# ATmega328-ED.net
KiCad netlist of a schematic drawn in Altium Designer
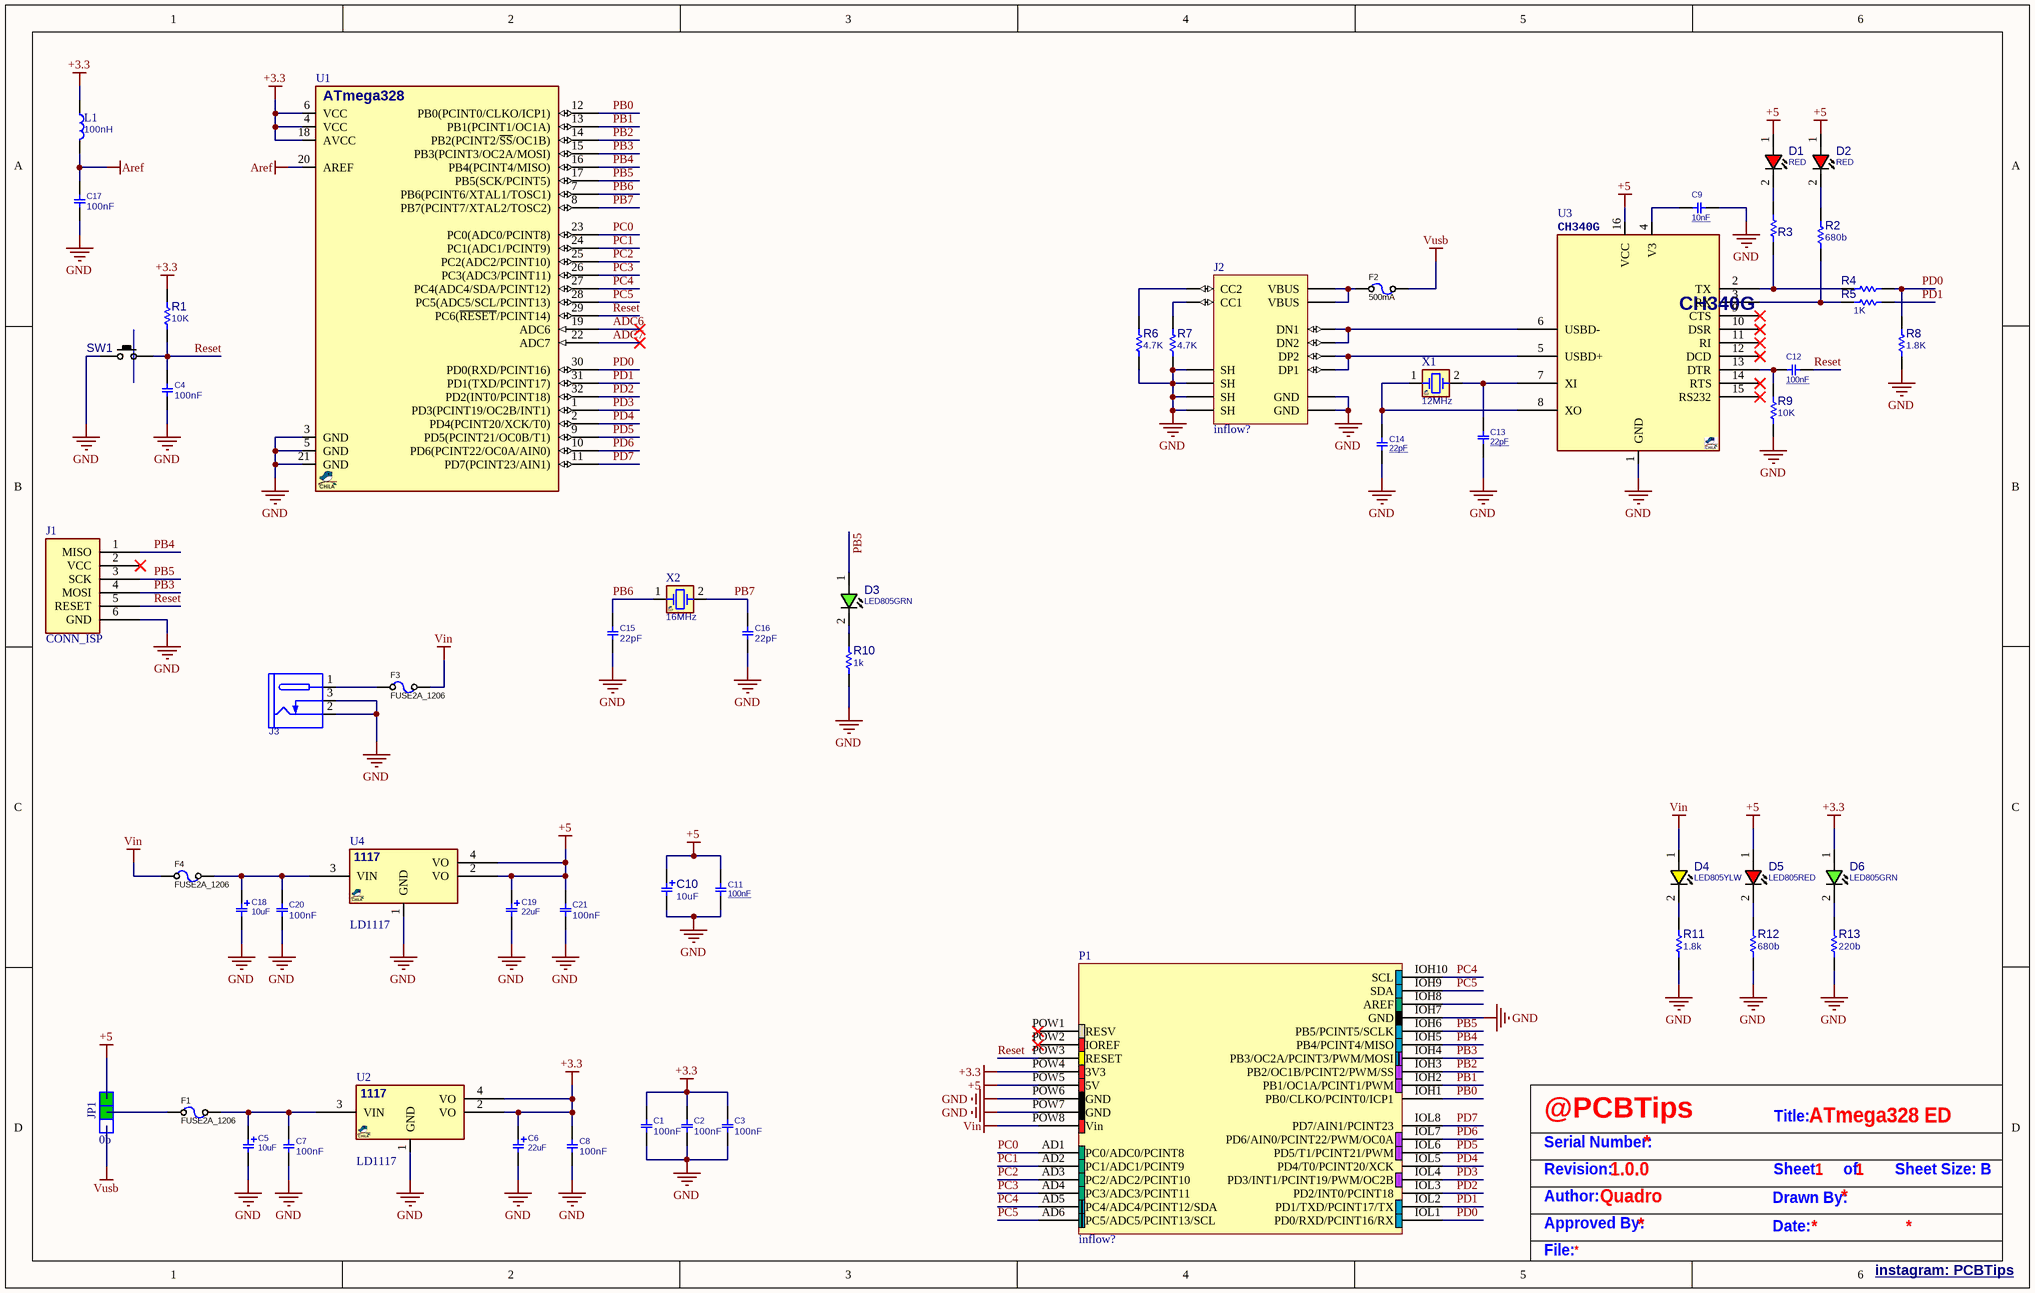
[diagram p0: ATmega328-ED.SchDoc]

(export (version "E")
  (design (tool "Eeschema 10.0.6"))
  (components
    (comp (ref "C1")
      (value "100nF")
      (footprint "C0805")
      (description "CAP, MLCC")
      (fields (field (name "MANF_P#") "MANF_PART#"))
      (libsource (lib "AVR_RCS") (part "CAP_SMD_MLCC_0805"))
    )
    (comp (ref "C2")
      (value "100nF")
      (footprint "C0805")
      (description "CAP, MLCC")
      (fields (field (name "MANF_P#") "MANF_PART#"))
      (libsource (lib "AVR_RCS") (part "CAP_SMD_MLCC_0805"))
    )
    (comp (ref "C3")
      (value "100nF")
      (footprint "C0805")
      (description "CAP, MLCC")
      (fields (field (name "MANF_P#") "MANF_PART#"))
      (libsource (lib "AVR_RCS") (part "CAP_SMD_MLCC_0805"))
    )
    (comp (ref "C4")
      (value "100nF")
      (footprint "C0805")
      (description "CAP, MLCC")
      (fields (field (name "MANF_P#") "MANF_PART#"))
      (libsource (lib "AVR_RCS") (part "CAP_SMD_MLCC_0805"))
    )
    (comp (ref "C5")
      (value "10uF")
      (footprint "C_TN_2012")
      (description "CAP, SMD, TAN")
      (fields (field (name "MANF") "VISHAY") (field (name "MANF_P#") "T55A106M6R3C0300"))
      (libsource (lib "AVR_RCS") (part "CAP_SMD_TAN_4"))
    )
    (comp (ref "C6")
      (value "22uF")
      (footprint "C_TN_2012")
      (description "CAP, SMD, TAN")
      (fields (field (name "MANF") "VISHAY") (field (name "MANF_P#") "T55A106M6R3C0300"))
      (libsource (lib "AVR_RCS") (part "CAP_SMD_TAN_4"))
    )
    (comp (ref "C7")
      (value "100nF")
      (footprint "C1206")
      (description "CAP, MLCC")
      (fields (field (name "MANF_P#") "MANF_PART#"))
      (libsource (lib "AVR_RCS") (part "CAP_SMD_MLCC_1206"))
    )
    (comp (ref "C8")
      (value "100nF")
      (footprint "C1206")
      (description "CAP, MLCC")
      (fields (field (name "MANF_P#") "MANF_PART#"))
      (libsource (lib "AVR_RCS") (part "CAP_SMD_MLCC_1206"))
    )
    (comp (ref "C9")
      (value "10nF")
      (footprint "C1206")
      (description "CAP, FILM, 680nF, 16V, Acryl, 20%, 1206")
      (fields (field (name "MANF") "Murata"))
      (libsource (lib "Chila_PCB") (part "CAP_SMD_FILM"))
    )
    (comp (ref "C10")
      (value "10uF")
      (footprint "C_EL_D4L5")
      (description "CAP, SMD, ELEC,")
      (fields (field (name "MANF_P#") "MANF_PART#") (field (name "MANF") "MANF"))
      (libsource (lib "ATMEGA328") (part "CAP_SMD_EL"))
    )
    (comp (ref "C11")
      (value "100nF")
      (footprint "C1206")
      (description "CAP, FILM, 680nF, 16V, Acryl, 20%, 1206")
      (fields (field (name "MANF") "Murata"))
      (libsource (lib "Chila_PCB") (part "CAP_SMD_FILM"))
    )
    (comp (ref "C12")
      (value "100nF")
      (footprint "C1206")
      (description "CAP, FILM, 680nF, 16V, Acryl, 20%, 1206")
      (fields (field (name "MANF") "Murata"))
      (libsource (lib "Chila_PCB") (part "CAP_SMD_FILM"))
    )
    (comp (ref "C13")
      (value "22pF")
      (footprint "C1206")
      (description "CAP, FILM, 680nF, 16V, Acryl, 20%, 1206")
      (fields (field (name "MANF") "Murata"))
      (libsource (lib "Chila_PCB") (part "CAP_SMD_FILM"))
    )
    (comp (ref "C14")
      (value "22pF")
      (footprint "C1206")
      (description "CAP, FILM, 680nF, 16V, Acryl, 20%, 1206")
      (fields (field (name "MANF") "Murata"))
      (libsource (lib "Chila_PCB") (part "CAP_SMD_FILM"))
    )
    (comp (ref "C15")
      (value "22pF")
      (footprint "C0805")
      (description "CAP, MLCC")
      (fields (field (name "MANF_P#") "MANF_PART#"))
      (libsource (lib "AVR_RCS") (part "CAP_SMD_MLCC_0805"))
    )
    (comp (ref "C16")
      (value "22pF")
      (footprint "C0805")
      (description "CAP, MLCC")
      (fields (field (name "MANF_P#") "MANF_PART#"))
      (libsource (lib "AVR_RCS") (part "CAP_SMD_MLCC_0805"))
    )
    (comp (ref "C17")
      (value "100nF")
      (footprint "C0805")
      (description "CAP, MLCC")
      (fields (field (name "MANF_P#") "MANF_PART#"))
      (libsource (lib "AVR_RCS") (part "CAP_SMD_MLCC_0805"))
    )
    (comp (ref "C18")
      (value "10uF")
      (footprint "C_TN_2012")
      (description "CAP, SMD, TAN")
      (fields (field (name "MANF") "VISHAY") (field (name "MANF_P#") "T55A106M6R3C0300"))
      (libsource (lib "AVR_RCS") (part "CAP_SMD_TAN_4"))
    )
    (comp (ref "C19")
      (value "22uF")
      (footprint "C_TN_2012")
      (description "CAP, SMD, TAN")
      (fields (field (name "MANF") "VISHAY") (field (name "MANF_P#") "T55A106M6R3C0300"))
      (libsource (lib "AVR_RCS") (part "CAP_SMD_TAN_4"))
    )
    (comp (ref "C20")
      (value "100nF")
      (footprint "C1206")
      (description "CAP, MLCC")
      (fields (field (name "MANF_P#") "MANF_PART#"))
      (libsource (lib "AVR_RCS") (part "CAP_SMD_MLCC_1206"))
    )
    (comp (ref "C21")
      (value "100nF")
      (footprint "C1206")
      (description "CAP, MLCC")
      (fields (field (name "MANF_P#") "MANF_PART#"))
      (libsource (lib "AVR_RCS") (part "CAP_SMD_MLCC_1206"))
    )
    (comp (ref "D1")
      (value "RED")
      (footprint "LED0805RED")
      (description "LED, SMD, 0805, RED")
      (fields (field (name "MANF") "MANF") (field (name "MANF_P#") "MANF_PART#"))
      (libsource (lib "Chila_PCB") (part "LED_SMD_0805_RED"))
    )
    (comp (ref "D2")
      (value "RED")
      (footprint "LED0805RED")
      (description "LED, SMD, 0805, RED")
      (fields (field (name "MANF") "MANF") (field (name "MANF_P#") "MANF_PART#"))
      (libsource (lib "Chila_PCB") (part "LED_SMD_0805_RED"))
    )
    (comp (ref "D3")
      (value "LED805GRN")
      (footprint "LED0805GRN")
      (description "LED, SMD, 0805, GREEN")
      (libsource (lib "Chila_PCB") (part "LED_SMD_0805_GRN"))
    )
    (comp (ref "D4")
      (value "LED805YLW")
      (footprint "LED0805YLW")
      (description "LED, SMD, 0805, YELLOW")
      (fields (field (name "MANF") "MANF") (field (name "MANF_P#") "MANF_PART#"))
      (libsource (lib "Chila_PCB") (part "LED_SMD_0805_YLW"))
    )
    (comp (ref "D5")
      (value "LED805RED")
      (footprint "LED0805RED")
      (description "LED, SMD, 0805, RED")
      (fields (field (name "MANF") "MANF") (field (name "MANF_P#") "MANF_PART#"))
      (libsource (lib "Chila_PCB") (part "LED_SMD_0805_RED"))
    )
    (comp (ref "D6")
      (value "LED805GRN")
      (footprint "LED0805GRN")
      (description "LED, SMD, 0805, GREEN")
      (libsource (lib "Chila_PCB") (part "LED_SMD_0805_GRN"))
    )
    (comp (ref "F1")
      (value "FUSE2A_1206")
      (footprint "F1206")
      (description "Fuse, 3A, 32VDC, 1206, SMD, Slow Blow")
      (fields (field (name "MANF") "Bourns") (field (name "MANF_P#") "SF-1206SP300-2"))
      (libsource (lib "AVR_RCS") (part "FUSE_3A_1206_SLOW"))
    )
    (comp (ref "F2")
      (value "500mA")
      (footprint "F1206")
      (description "Fuse, 3A, 32VDC, 1206, SMD, Slow Blow")
      (fields (field (name "MANF") "Bourns") (field (name "MANF_P#") "SF-1206SP300-2"))
      (libsource (lib "Chila_PCB") (part "FUSE_3A_1206_SLOW"))
    )
    (comp (ref "F3")
      (value "FUSE2A_1206")
      (footprint "F1206")
      (description "Fuse, 3A, 32VDC, 1206, SMD, Slow Blow")
      (fields (field (name "MANF") "Bourns") (field (name "MANF_P#") "SF-1206SP300-2"))
      (libsource (lib "AVR_RCS") (part "FUSE_3A_1206_SLOW"))
    )
    (comp (ref "F4")
      (value "FUSE2A_1206")
      (footprint "F1206")
      (description "Fuse, 3A, 32VDC, 1206, SMD, Slow Blow")
      (fields (field (name "MANF") "Bourns") (field (name "MANF_P#") "SF-1206SP300-2"))
      (libsource (lib "AVR_RCS") (part "FUSE_3A_1206_SLOW"))
    )
    (comp (ref "J1")
      (value "CONN_ISP")
      (footprint "IDC_2X3")
      (description "CONN, ISP, AVR , HEADER BOX")
      (libsource (lib "AVR_RCS") (part "CONN_AVR_ISP_IDC6"))
    )
    (comp (ref "J2")
      (value "12b")
      (footprint "HRO_TYPE-C-31-M-12 - Extended")
      (description "USB C Female Connector")
      (fields (field (name "INFLOW") "inflow?") (field (name "VALIDATION") "Valid"))
      (libsource (lib "ATMEGA328") (part "Con_USB_C"))
    )
    (comp (ref "J3")
      (value "DC_POWER_JACK")
      (footprint "JAC_PWR2")
      (description "CONN, PWR JACK DC, PLUG DIAM 2.0MM RA THD")
      (fields
        (field (name "MANF") "CUI STACK")
        (field (name "MANF_P#") "PJ-202A, PJ-002AH, PJ-102AH, KLDX-0202")
      )
      (libsource (lib "ATMEGA328") (part "CONN_PWR_JACKR2"))
    )
    (comp (ref "JP1")
      (value "0b")
      (footprint "jumper selector")
      (description "Jumper Selector")
      (fields (field (name "VALIDATION") "NT"))
      (libsource (lib "ATMEGA328") (part "SW_Other_JSelector_Dip"))
    )
    (comp (ref "L1")
      (value "100nH")
      (footprint "L0805")
      (description "INDUCTOR, SMD")
      (fields (field (name "MANF") "EPCOS / TDK") (field (name "MANF_P#") "B82498F3331J"))
      (libsource (lib "ATMEGA328") (part "IND_SMD_330nH_0.2A"))
    )
    (comp (ref "P1")
      (value "UNO")
      (footprint "ARDUINO_UNO_CONNECTOR")
      (description "Arduino UNO Connector")
      (fields (field (name "INFLOW") "inflow?") (field (name "VALIDATION") "NT"))
      (libsource (lib "ATMEGA328") (part "Con_Arduino_UNO_Con"))
    )
    (comp (ref "R1")
      (value "10K")
      (footprint "R0805")
      (description "RESISTOR, SMD")
      (libsource (lib "AVR_RCS") (part "RES_SMD_0805"))
    )
    (comp (ref "R2")
      (value "680b")
      (footprint "R0805")
      (description "RESISTOR, SMD")
      (libsource (lib "Chila_PCB") (part "RES_SMD_0805"))
    )
    (comp (ref "R3")
      (value "680b")
      (footprint "R0805")
      (description "RESISTOR, SMD")
      (libsource (lib "Chila_PCB") (part "RES_SMD_0805"))
    )
    (comp (ref "R4")
      (value "1K")
      (footprint "R0805")
      (description "RESISTOR, SMD")
      (libsource (lib "Chila_PCB") (part "RES_SMD_0805"))
    )
    (comp (ref "R5")
      (value "1K")
      (footprint "R0805")
      (description "RESISTOR, SMD")
      (libsource (lib "Chila_PCB") (part "RES_SMD_0805"))
    )
    (comp (ref "R6")
      (value "4.7K")
      (footprint "R0805")
      (description "RESISTOR, SMD")
      (libsource (lib "Chila_PCB") (part "RES_SMD_0805"))
    )
    (comp (ref "R7")
      (value "4.7K")
      (footprint "R0805")
      (description "RESISTOR, SMD")
      (libsource (lib "Chila_PCB") (part "RES_SMD_0805"))
    )
    (comp (ref "R8")
      (value "1.8K")
      (footprint "R0805")
      (description "RESISTOR, SMD")
      (libsource (lib "Chila_PCB") (part "RES_SMD_0805"))
    )
    (comp (ref "R9")
      (value "10K")
      (footprint "R0805")
      (description "RESISTOR, SMD")
      (libsource (lib "Chila_PCB") (part "RES_SMD_0805"))
    )
    (comp (ref "R10")
      (value "1k")
      (footprint "R0805")
      (description "RESISTOR, SMD")
      (libsource (lib "Chila_PCB") (part "RES_SMD_0805"))
    )
    (comp (ref "R11")
      (value "1.8k")
      (footprint "R0805")
      (description "RESISTOR, SMD")
      (libsource (lib "Chila_PCB") (part "RES_SMD_0805"))
    )
    (comp (ref "R12")
      (value "680b")
      (footprint "R0805")
      (description "RESISTOR, SMD")
      (libsource (lib "Chila_PCB") (part "RES_SMD_0805"))
    )
    (comp (ref "R13")
      (value "220b")
      (footprint "R0805")
      (description "RESISTOR, SMD")
      (libsource (lib "Chila_PCB") (part "RES_SMD_0805"))
    )
    (comp (ref "SW1")
      (value "PUSHBUTTON")
      (footprint "SWPBS_SPST_6X3X2")
      (description "SWITCH, PUSH BUTTON, TACTILE, SMD, SPST, 6X3.5X2.5mm")
      (fields (field (name "MANF") "C&K") (field (name "MANF_P#") "RS-282G05A3-SM RT"))
      (libsource (lib "AVR_RCS") (part "SWPBS_SPST_6X3X2_RS282"))
    )
    (comp (ref "U1")
      (value "ATMEGA328")
      (footprint "QFG80_32")
      (description "MCU, AVR, 8-Bit, 16KB, 1KB RAM, 20MHz")
      (fields (field (name "MANF_P#") "ATMEGA328-AU") (field (name "MANF") "ATMEL/MICROCHIP"))
      (libsource (lib "AVR_RCS") (part "ATMEGA328_QFP32"))
    )
    (comp (ref "U2")
      (value "LD1117")
      (footprint "SOT223_4")
      (description "REG, Linear, LDO1V, 0.8A, SOT-223")
      (fields
        (field (name "MANF_P#") "LD1117, LM1117, AMS1117, TLV1117, REG1117, NCP1117, LT1117, SPX1117")
        (field (name "MANF") "TI, ON, ST")
      )
      (libsource (lib "AVR_RCS") (part "VREG_1117_SOT223"))
    )
    (comp (ref "U3")
      (value "CH340G")
      (footprint "SO_16")
      (description "USB-UART")
      (libsource (lib "Chila_PCB") (part "CH340G_SOP16"))
    )
    (comp (ref "U4")
      (value "LD1117")
      (footprint "SOT223_4")
      (description "REG, Linear, LDO1V, 0.8A, SOT-223")
      (fields
        (field (name "MANF_P#") "LD1117, LM1117, AMS1117, TLV1117, REG1117, NCP1117, LT1117, SPX1117")
        (field (name "MANF") "TI, ON, ST")
      )
      (libsource (lib "AVR_RCS") (part "VREG_1117_SOT223"))
    )
    (comp (ref "X1")
      (value "12MHz")
      (footprint "XTL_2_11X5")
      (description "Crystal MOST POPULAR ABL HC49 PACKAGE")
      (fields (field (name "MANF") "ABRACON") (field (name "MANF_P#") "ABLS-8.000MHZ-B4-T"))
      (libsource (lib "Chila_PCB") (part "XTL_2_HC49_8MHz_SMD"))
    )
    (comp (ref "X2")
      (value "16MHz")
      (footprint "XTL_2_11X5")
      (description "Crystal MOST POPULAR ABL HC49 PACKAGE")
      (libsource (lib "ATMEGA328") (part "XTL_2_HC49_SMD"))
    )
  )
  (nets
    (net (code "1") (name "+3.3") (class "Default")
      (node (ref "C1") (pin "2") (pinfunction "2_2") (pintype "passive"))
      (node (ref "C2") (pin "2") (pinfunction "2_2") (pintype "passive"))
      (node (ref "C3") (pin "2") (pinfunction "2_2") (pintype "passive"))
      (node (ref "C6") (pin "1") (pinfunction "1_1") (pintype "passive"))
      (node (ref "C8") (pin "1") (pinfunction "1_1") (pintype "passive"))
      (node (ref "D6") (pin "1") (pinfunction "ANODE_1") (pintype "passive"))
      (node (ref "L1") (pin "1") (pinfunction "1_1") (pintype "passive"))
      (node (ref "P1") (pin "POW4") (pinfunction "3V3_POW4") (pintype "passive"))
      (node (ref "R1") (pin "2") (pinfunction "2_2") (pintype "passive"))
      (node (ref "U1") (pin "18") (pinfunction "AVCC_18") (pintype "power_in"))
      (node (ref "U1") (pin "4") (pinfunction "VCC_4") (pintype "power_in"))
      (node (ref "U1") (pin "6") (pinfunction "VCC_6") (pintype "power_in"))
      (node (ref "U2") (pin "2") (pinfunction "VO_2") (pintype "passive"))
      (node (ref "U2") (pin "4") (pinfunction "VO_4") (pintype "passive"))
    )
    (net (code "2") (name "+5") (class "Default")
      (node (ref "C10") (pin "1") (pinfunction "1_1") (pintype "passive"))
      (node (ref "C11") (pin "2") (pinfunction "2_2") (pintype "passive"))
      (node (ref "C19") (pin "1") (pinfunction "1_1") (pintype "passive"))
      (node (ref "C21") (pin "1") (pinfunction "1_1") (pintype "passive"))
      (node (ref "D1") (pin "1") (pinfunction "ANODE_1") (pintype "passive"))
      (node (ref "D2") (pin "1") (pinfunction "ANODE_1") (pintype "passive"))
      (node (ref "D5") (pin "1") (pinfunction "ANODE_1") (pintype "passive"))
      (node (ref "JP1") (pin "1") (pinfunction "1_1") (pintype "passive"))
      (node (ref "P1") (pin "POW5") (pinfunction "5V_POW5") (pintype "passive"))
      (node (ref "U3") (pin "16") (pinfunction "VCC_16") (pintype "passive"))
      (node (ref "U4") (pin "2") (pinfunction "VO_2") (pintype "passive"))
      (node (ref "U4") (pin "4") (pinfunction "VO_4") (pintype "passive"))
    )
    (net (code "3") (name "/ADC6") (class "Default")
      (node (ref "U1") (pin "19") (pinfunction "ADC6_19") (pintype "input+no_connect"))
    )
    (net (code "4") (name "/ADC7") (class "Default")
      (node (ref "U1") (pin "22") (pinfunction "ADC7_22") (pintype "input+no_connect"))
    )
    (net (code "5") (name "/PB0") (class "Default")
      (node (ref "P1") (pin "IOH1") (pinfunction "PB0/CLKO/PCINT0/ICP1_IOH1") (pintype "passive"))
      (node (ref "U1") (pin "12") (pinfunction "PB0(PCINT0/CLKO/ICP1)_12") (pintype "bidirectional"))
    )
    (net (code "6") (name "/PB1") (class "Default")
      (node (ref "P1") (pin "IOH2") (pinfunction "PB1/OC1A/PCINT1/PWM_IOH2") (pintype "passive"))
      (node (ref "U1") (pin "13") (pinfunction "PB1(PCINT1/OC1A)_13") (pintype "bidirectional"))
    )
    (net (code "7") (name "/PB2") (class "Default")
      (node (ref "P1") (pin "IOH3") (pinfunction "PB2/OC1B/PCINT2/PWM/SS_IOH3") (pintype "passive"))
      (node (ref "U1") (pin "14") (pinfunction "PB2(PCINT2/~{SS}/OC1B)_14") (pintype "bidirectional"))
    )
    (net (code "8") (name "/PB3") (class "Default")
      (node (ref "J1") (pin "4") (pinfunction "MOSI_4") (pintype "passive"))
      (node (ref "P1") (pin "IOH4") (pinfunction "PB3/OC2A/PCINT3/PWM/MOSI_IOH4") (pintype "passive"))
      (node (ref "U1") (pin "15") (pinfunction "PB3(PCINT3/OC2A/MOSI)_15") (pintype "bidirectional"))
    )
    (net (code "9") (name "/PB4") (class "Default")
      (node (ref "J1") (pin "1") (pinfunction "MISO_1") (pintype "passive"))
      (node (ref "P1") (pin "IOH5") (pinfunction "PB4/PCINT4/MISO_IOH5") (pintype "passive"))
      (node (ref "U1") (pin "16") (pinfunction "PB4(PCINT4/MISO)_16") (pintype "bidirectional"))
    )
    (net (code "10") (name "/PB5") (class "Default")
      (node (ref "D3") (pin "1") (pinfunction "ANODE_1") (pintype "passive"))
      (node (ref "J1") (pin "3") (pinfunction "SCK_3") (pintype "passive"))
      (node (ref "P1") (pin "IOH6") (pinfunction "PB5/PCINT5/SCLK_IOH6") (pintype "passive"))
      (node (ref "U1") (pin "17") (pinfunction "PB5(SCK/PCINT5)_17") (pintype "bidirectional"))
    )
    (net (code "11") (name "/PB6") (class "Default")
      (node (ref "C15") (pin "2") (pinfunction "2_2") (pintype "passive"))
      (node (ref "U1") (pin "7") (pinfunction "PB6(PCINT6/XTAL1/TOSC1)_7") (pintype "bidirectional"))
      (node (ref "X2") (pin "1") (pinfunction "OSC1_1") (pintype "passive"))
    )
    (net (code "12") (name "/PB7") (class "Default")
      (node (ref "C16") (pin "2") (pinfunction "2_2") (pintype "passive"))
      (node (ref "U1") (pin "8") (pinfunction "PB7(PCINT7/XTAL2/TOSC2)_8") (pintype "bidirectional"))
      (node (ref "X2") (pin "2") (pinfunction "OSC2_2") (pintype "passive"))
    )
    (net (code "13") (name "/PC0") (class "Default")
      (node (ref "P1") (pin "AD1") (pinfunction "PC0/ADC0/PCINT8_AD1") (pintype "passive"))
      (node (ref "U1") (pin "23") (pinfunction "PC0(ADC0/PCINT8)_23") (pintype "bidirectional"))
    )
    (net (code "14") (name "/PC1") (class "Default")
      (node (ref "P1") (pin "AD2") (pinfunction "PC1/ADC1/PCINT9_AD2") (pintype "passive"))
      (node (ref "U1") (pin "24") (pinfunction "PC1(ADC1/PCINT9)_24") (pintype "bidirectional"))
    )
    (net (code "15") (name "/PC2") (class "Default")
      (node (ref "P1") (pin "AD3") (pinfunction "PC2/ADC2/PCINT10_AD3") (pintype "passive"))
      (node (ref "U1") (pin "25") (pinfunction "PC2(ADC2/PCINT10)_25") (pintype "bidirectional"))
    )
    (net (code "16") (name "/PC3") (class "Default")
      (node (ref "P1") (pin "AD4") (pinfunction "PC3/ADC3/PCINT11_AD4") (pintype "passive"))
      (node (ref "U1") (pin "26") (pinfunction "PC3(ADC3/PCINT11)_26") (pintype "bidirectional"))
    )
    (net (code "17") (name "/PC4") (class "Default")
      (node (ref "P1") (pin "AD5") (pinfunction "PC4/ADC4/PCINT12/SDA_AD5") (pintype "passive"))
      (node (ref "P1") (pin "IOH10") (pinfunction "SCL_IOH10") (pintype "passive"))
      (node (ref "U1") (pin "27") (pinfunction "PC4(ADC4/SDA/PCINT12)_27") (pintype "bidirectional"))
    )
    (net (code "18") (name "/PC5") (class "Default")
      (node (ref "P1") (pin "AD6") (pinfunction "PC5/ADC5/PCINT13/SCL_AD6") (pintype "passive"))
      (node (ref "P1") (pin "IOH9") (pinfunction "SDA_IOH9") (pintype "passive"))
      (node (ref "U1") (pin "28") (pinfunction "PC5(ADC5/SCL/PCINT13)_28") (pintype "bidirectional"))
    )
    (net (code "19") (name "/PD0") (class "Default")
      (node (ref "P1") (pin "IOL1") (pinfunction "PD0/RXD/PCINT16/RX_IOL1") (pintype "passive"))
      (node (ref "R4") (pin "2") (pinfunction "2_2") (pintype "passive"))
      (node (ref "R8") (pin "2") (pinfunction "2_2") (pintype "passive"))
      (node (ref "U1") (pin "30") (pinfunction "PD0(RXD/PCINT16)_30") (pintype "bidirectional"))
    )
    (net (code "20") (name "/PD1") (class "Default")
      (node (ref "P1") (pin "IOL2") (pinfunction "PD1/TXD/PCINT17/TX_IOL2") (pintype "passive"))
      (node (ref "R5") (pin "2") (pinfunction "2_2") (pintype "passive"))
      (node (ref "U1") (pin "31") (pinfunction "PD1(TXD/PCINT17)_31") (pintype "bidirectional"))
    )
    (net (code "21") (name "/PD2") (class "Default")
      (node (ref "P1") (pin "IOL3") (pinfunction "PD2/INT0/PCINT18_IOL3") (pintype "passive"))
      (node (ref "U1") (pin "32") (pinfunction "PD2(INT0/PCINT18)_32") (pintype "bidirectional"))
    )
    (net (code "22") (name "/PD3") (class "Default")
      (node (ref "P1") (pin "IOL4") (pinfunction "PD3/INT1/PCINT19/PWM/OC2B_IOL4") (pintype "passive"))
      (node (ref "U1") (pin "1") (pinfunction "PD3(PCINT19/OC2B/INT1)_1") (pintype "bidirectional"))
    )
    (net (code "23") (name "/PD4") (class "Default")
      (node (ref "P1") (pin "IOL5") (pinfunction "PD4/T0/PCINT20/XCK_IOL5") (pintype "passive"))
      (node (ref "U1") (pin "2") (pinfunction "PD4(PCINT20/XCK/T0)_2") (pintype "bidirectional"))
    )
    (net (code "24") (name "/PD5") (class "Default")
      (node (ref "P1") (pin "IOL6") (pinfunction "PD5/T1/PCINT21/PWM_IOL6") (pintype "passive"))
      (node (ref "U1") (pin "9") (pinfunction "PD5(PCINT21/OC0B/T1)_9") (pintype "bidirectional"))
    )
    (net (code "25") (name "/PD6") (class "Default")
      (node (ref "P1") (pin "IOL7") (pinfunction "PD6/AIN0/PCINT22/PWM/OC0A_IOL7") (pintype "passive"))
      (node (ref "U1") (pin "10") (pinfunction "PD6(PCINT22/OC0A/AIN0)_10") (pintype "bidirectional"))
    )
    (net (code "26") (name "/PD7") (class "Default")
      (node (ref "P1") (pin "IOL8") (pinfunction "PD7/AIN1/PCINT23_IOL8") (pintype "passive"))
      (node (ref "U1") (pin "11") (pinfunction "PD7(PCINT23/AIN1)_11") (pintype "bidirectional"))
    )
    (net (code "27") (name "/Reset") (class "Default")
      (node (ref "C12") (pin "1") (pinfunction "1_1") (pintype "passive"))
      (node (ref "C4") (pin "2") (pinfunction "2_2") (pintype "passive"))
      (node (ref "J1") (pin "5") (pinfunction "RESET_5") (pintype "passive"))
      (node (ref "P1") (pin "POW3") (pinfunction "RESET_POW3") (pintype "passive"))
      (node (ref "R1") (pin "1") (pinfunction "1_1") (pintype "passive"))
      (node (ref "SW1") (pin "2") (pinfunction "P3_2") (pintype "passive"))
      (node (ref "U1") (pin "29") (pinfunction "PC6(~{RESET}/PCINT14)_29") (pintype "bidirectional"))
    )
    (net (code "28") (name "Aref") (class "Default")
      (node (ref "C17") (pin "2") (pinfunction "2_2") (pintype "passive"))
      (node (ref "L1") (pin "2") (pinfunction "2_2") (pintype "passive"))
      (node (ref "U1") (pin "20") (pinfunction "AREF_20") (pintype "passive"))
    )
    (net (code "29") (name "GND") (class "Default")
      (node (ref "C1") (pin "1") (pinfunction "1_1") (pintype "passive"))
      (node (ref "C10") (pin "2") (pinfunction "2_2") (pintype "passive"))
      (node (ref "C11") (pin "1") (pinfunction "1_1") (pintype "passive"))
      (node (ref "C13") (pin "1") (pinfunction "1_1") (pintype "passive"))
      (node (ref "C14") (pin "1") (pinfunction "1_1") (pintype "passive"))
      (node (ref "C15") (pin "1") (pinfunction "1_1") (pintype "passive"))
      (node (ref "C16") (pin "1") (pinfunction "1_1") (pintype "passive"))
      (node (ref "C17") (pin "1") (pinfunction "1_1") (pintype "passive"))
      (node (ref "C18") (pin "2") (pinfunction "2_2") (pintype "passive"))
      (node (ref "C19") (pin "2") (pinfunction "2_2") (pintype "passive"))
      (node (ref "C2") (pin "1") (pinfunction "1_1") (pintype "passive"))
      (node (ref "C20") (pin "2") (pinfunction "2_2") (pintype "passive"))
      (node (ref "C21") (pin "2") (pinfunction "2_2") (pintype "passive"))
      (node (ref "C3") (pin "1") (pinfunction "1_1") (pintype "passive"))
      (node (ref "C4") (pin "1") (pinfunction "1_1") (pintype "passive"))
      (node (ref "C5") (pin "2") (pinfunction "2_2") (pintype "passive"))
      (node (ref "C6") (pin "2") (pinfunction "2_2") (pintype "passive"))
      (node (ref "C7") (pin "2") (pinfunction "2_2") (pintype "passive"))
      (node (ref "C8") (pin "2") (pinfunction "2_2") (pintype "passive"))
      (node (ref "C9") (pin "1") (pinfunction "1_1") (pintype "passive"))
      (node (ref "J1") (pin "6") (pinfunction "GND_6") (pintype "passive"))
      (node (ref "J2") (pin "A1_B12") (pinfunction "GND_A1_B12") (pintype "power_in"))
      (node (ref "J2") (pin "B1_A12") (pinfunction "GND_B1_A12") (pintype "power_in"))
      (node (ref "J2") (pin "S1") (pinfunction "SH_S1") (pintype "passive"))
      (node (ref "J2") (pin "S2") (pinfunction "SH_S2") (pintype "passive"))
      (node (ref "J2") (pin "S3") (pinfunction "SH_S3") (pintype "passive"))
      (node (ref "J2") (pin "S4") (pinfunction "SH_S4") (pintype "passive"))
      (node (ref "J3") (pin "2") (pinfunction "SLEEVE_2") (pintype "power_in"))
      (node (ref "J3") (pin "3") (pinfunction "INSERTION_DET_3") (pintype "power_in"))
      (node (ref "P1") (pin "IOH7") (pinfunction "GND_IOH7") (pintype "passive"))
      (node (ref "P1") (pin "POW6") (pinfunction "GND_POW6") (pintype "passive"))
      (node (ref "P1") (pin "POW7") (pinfunction "GND_POW7") (pintype "passive"))
      (node (ref "R10") (pin "1") (pinfunction "1_1") (pintype "passive"))
      (node (ref "R11") (pin "1") (pinfunction "1_1") (pintype "passive"))
      (node (ref "R12") (pin "1") (pinfunction "1_1") (pintype "passive"))
      (node (ref "R13") (pin "1") (pinfunction "1_1") (pintype "passive"))
      (node (ref "R6") (pin "1") (pinfunction "1_1") (pintype "passive"))
      (node (ref "R7") (pin "1") (pinfunction "1_1") (pintype "passive"))
      (node (ref "R8") (pin "1") (pinfunction "1_1") (pintype "passive"))
      (node (ref "R9") (pin "1") (pinfunction "1_1") (pintype "passive"))
      (node (ref "SW1") (pin "1") (pinfunction "P1_1") (pintype "passive"))
      (node (ref "U1") (pin "21") (pinfunction "GND_21") (pintype "power_in"))
      (node (ref "U1") (pin "3") (pinfunction "GND_3") (pintype "power_in"))
      (node (ref "U1") (pin "5") (pinfunction "GND_5") (pintype "power_in"))
      (node (ref "U2") (pin "1") (pinfunction "GND_1") (pintype "passive"))
      (node (ref "U3") (pin "1") (pinfunction "GND_1") (pintype "passive"))
      (node (ref "U4") (pin "1") (pinfunction "GND_1") (pintype "passive"))
    )
    (net (code "30") (name "Net-(D1-CATHODE)") (class "Default")
      (node (ref "D1") (pin "2") (pinfunction "CATHODE_2") (pintype "passive"))
      (node (ref "R3") (pin "2") (pinfunction "2_2") (pintype "passive"))
    )
    (net (code "31") (name "Net-(D2-CATHODE)") (class "Default")
      (node (ref "D2") (pin "2") (pinfunction "CATHODE_2") (pintype "passive"))
      (node (ref "R2") (pin "2") (pinfunction "2_2") (pintype "passive"))
    )
    (net (code "32") (name "Net-(D3-CATHODE)") (class "Default")
      (node (ref "D3") (pin "2") (pinfunction "CATHODE_2") (pintype "passive"))
      (node (ref "R10") (pin "2") (pinfunction "2_2") (pintype "passive"))
    )
    (net (code "33") (name "Net-(D4-CATHODE)") (class "Default")
      (node (ref "D4") (pin "2") (pinfunction "CATHODE_2") (pintype "passive"))
      (node (ref "R11") (pin "2") (pinfunction "2_2") (pintype "passive"))
    )
    (net (code "34") (name "Net-(D5-CATHODE)") (class "Default")
      (node (ref "D5") (pin "2") (pinfunction "CATHODE_2") (pintype "passive"))
      (node (ref "R12") (pin "2") (pinfunction "2_2") (pintype "passive"))
    )
    (net (code "35") (name "Net-(D6-CATHODE)") (class "Default")
      (node (ref "D6") (pin "2") (pinfunction "CATHODE_2") (pintype "passive"))
      (node (ref "R13") (pin "2") (pinfunction "2_2") (pintype "passive"))
    )
    (net (code "36") (name "Net-(F1-Pad1)") (class "Default")
      (node (ref "F1") (pin "1") (pinfunction "1_1") (pintype "passive"))
      (node (ref "JP1") (pin "2") (pinfunction "2_2") (pintype "passive"))
    )
    (net (code "37") (name "Net-(F2-Pad1)") (class "Default")
      (node (ref "F2") (pin "1") (pinfunction "1_1") (pintype "passive"))
      (node (ref "J2") (pin "A4_B9") (pinfunction "VBUS_A4_B9") (pintype "power_in"))
      (node (ref "J2") (pin "B4_A9") (pinfunction "VBUS_B4_A9") (pintype "power_in"))
    )
    (net (code "38") (name "Net-(J2-CC1)") (class "Default")
      (node (ref "J2") (pin "A5") (pinfunction "CC1_A5") (pintype "bidirectional"))
      (node (ref "R7") (pin "2") (pinfunction "2_2") (pintype "passive"))
    )
    (net (code "39") (name "Net-(J2-CC2)") (class "Default")
      (node (ref "J2") (pin "B5") (pinfunction "CC2_B5") (pintype "bidirectional"))
      (node (ref "R6") (pin "2") (pinfunction "2_2") (pintype "passive"))
    )
    (net (code "40") (name "Net-(J2-DN1)") (class "Default")
      (node (ref "J2") (pin "A7") (pinfunction "DN1_A7") (pintype "bidirectional"))
      (node (ref "J2") (pin "B7") (pinfunction "DN2_B7") (pintype "bidirectional"))
      (node (ref "U3") (pin "6") (pinfunction "USBD-_6") (pintype "passive"))
    )
    (net (code "41") (name "Net-(J2-DP1)") (class "Default")
      (node (ref "J2") (pin "A6") (pinfunction "DP1_A6") (pintype "bidirectional"))
      (node (ref "J2") (pin "B6") (pinfunction "DP2_B6") (pintype "bidirectional"))
      (node (ref "U3") (pin "5") (pinfunction "USBD+_5") (pintype "passive"))
    )
    (net (code "42") (name "Net-(J3-TIP)") (class "Default")
      (node (ref "F3") (pin "1") (pinfunction "1_1") (pintype "passive"))
      (node (ref "J3") (pin "1") (pinfunction "TIP_1") (pintype "power_in"))
    )
    (net (code "43") (name "Net-(U2-VIN)") (class "Default")
      (node (ref "C5") (pin "1") (pinfunction "1_1") (pintype "passive"))
      (node (ref "C7") (pin "1") (pinfunction "1_1") (pintype "passive"))
      (node (ref "F1") (pin "2") (pinfunction "2_2") (pintype "passive"))
      (node (ref "U2") (pin "3") (pinfunction "VIN_3") (pintype "passive"))
    )
    (net (code "44") (name "Net-(U3-DTR)") (class "Default")
      (node (ref "C12") (pin "2") (pinfunction "2_2") (pintype "passive"))
      (node (ref "R9") (pin "2") (pinfunction "2_2") (pintype "passive"))
      (node (ref "U3") (pin "13") (pinfunction "DTR_13") (pintype "passive"))
    )
    (net (code "45") (name "Net-(U3-RX)") (class "Default")
      (node (ref "R2") (pin "1") (pinfunction "1_1") (pintype "passive"))
      (node (ref "R5") (pin "1") (pinfunction "1_1") (pintype "passive"))
      (node (ref "U3") (pin "3") (pinfunction "RX_3") (pintype "passive"))
    )
    (net (code "46") (name "Net-(U3-TX)") (class "Default")
      (node (ref "R3") (pin "1") (pinfunction "1_1") (pintype "passive"))
      (node (ref "R4") (pin "1") (pinfunction "1_1") (pintype "passive"))
      (node (ref "U3") (pin "2") (pinfunction "TX_2") (pintype "passive"))
    )
    (net (code "47") (name "Net-(U3-V3)") (class "Default")
      (node (ref "C9") (pin "2") (pinfunction "2_2") (pintype "passive"))
      (node (ref "U3") (pin "4") (pinfunction "V3_4") (pintype "passive"))
    )
    (net (code "48") (name "Net-(U3-XI)") (class "Default")
      (node (ref "C13") (pin "2") (pinfunction "2_2") (pintype "passive"))
      (node (ref "U3") (pin "7") (pinfunction "XI_7") (pintype "passive"))
      (node (ref "X1") (pin "2") (pinfunction "OSC2_2") (pintype "passive"))
    )
    (net (code "49") (name "Net-(U3-XO)") (class "Default")
      (node (ref "C14") (pin "2") (pinfunction "2_2") (pintype "passive"))
      (node (ref "U3") (pin "8") (pinfunction "XO_8") (pintype "passive"))
      (node (ref "X1") (pin "1") (pinfunction "OSC1_1") (pintype "passive"))
    )
    (net (code "50") (name "Net-(U4-VIN)") (class "Default")
      (node (ref "C18") (pin "1") (pinfunction "1_1") (pintype "passive"))
      (node (ref "C20") (pin "1") (pinfunction "1_1") (pintype "passive"))
      (node (ref "F4") (pin "2") (pinfunction "2_2") (pintype "passive"))
      (node (ref "U4") (pin "3") (pinfunction "VIN_3") (pintype "passive"))
    )
    (net (code "51") (name "Vin") (class "Default")
      (node (ref "D4") (pin "1") (pinfunction "ANODE_1") (pintype "passive"))
      (node (ref "F3") (pin "2") (pinfunction "2_2") (pintype "passive"))
      (node (ref "F4") (pin "1") (pinfunction "1_1") (pintype "passive"))
      (node (ref "P1") (pin "POW8") (pinfunction "Vin_POW8") (pintype "passive"))
    )
    (net (code "52") (name "Vusb") (class "Default")
      (node (ref "F2") (pin "2") (pinfunction "2_2") (pintype "passive"))
      (node (ref "JP1") (pin "3") (pinfunction "3_3") (pintype "passive"))
    )
    (net (code "53") (name "unconnected-(J1-VCC-Pad2)") (class "Default")
      (node (ref "J1") (pin "2") (pinfunction "VCC_2") (pintype "passive+no_connect"))
    )
    (net (code "54") (name "unconnected-(P1-AREF-PadIOH8)") (class "Default")
      (node (ref "P1") (pin "IOH8") (pinfunction "AREF_IOH8") (pintype "passive"))
    )
    (net (code "55") (name "unconnected-(P1-IOREF-PadPOW2)") (class "Default")
      (node (ref "P1") (pin "POW2") (pinfunction "IOREF_POW2") (pintype "passive+no_connect"))
    )
    (net (code "56") (name "unconnected-(P1-RESV-PadPOW1)") (class "Default")
      (node (ref "P1") (pin "POW1") (pinfunction "RESV_POW1") (pintype "passive+no_connect"))
    )
    (net (code "57") (name "unconnected-(U3-CTS-Pad9)") (class "Default")
      (node (ref "U3") (pin "9") (pinfunction "CTS_9") (pintype "passive+no_connect"))
    )
    (net (code "58") (name "unconnected-(U3-DCD-Pad12)") (class "Default")
      (node (ref "U3") (pin "12") (pinfunction "DCD_12") (pintype "passive+no_connect"))
    )
    (net (code "59") (name "unconnected-(U3-DSR-Pad10)") (class "Default")
      (node (ref "U3") (pin "10") (pinfunction "DSR_10") (pintype "passive+no_connect"))
    )
    (net (code "60") (name "unconnected-(U3-RI-Pad11)") (class "Default")
      (node (ref "U3") (pin "11") (pinfunction "RI_11") (pintype "passive+no_connect"))
    )
    (net (code "61") (name "unconnected-(U3-RS232-Pad15)") (class "Default")
      (node (ref "U3") (pin "15") (pinfunction "RS232_15") (pintype "passive+no_connect"))
    )
    (net (code "62") (name "unconnected-(U3-RTS-Pad14)") (class "Default")
      (node (ref "U3") (pin "14") (pinfunction "RTS_14") (pintype "passive+no_connect"))
    )
  )
)
